# 9833YUANLI.net
KiCad netlist of a schematic drawn in EasyEDA
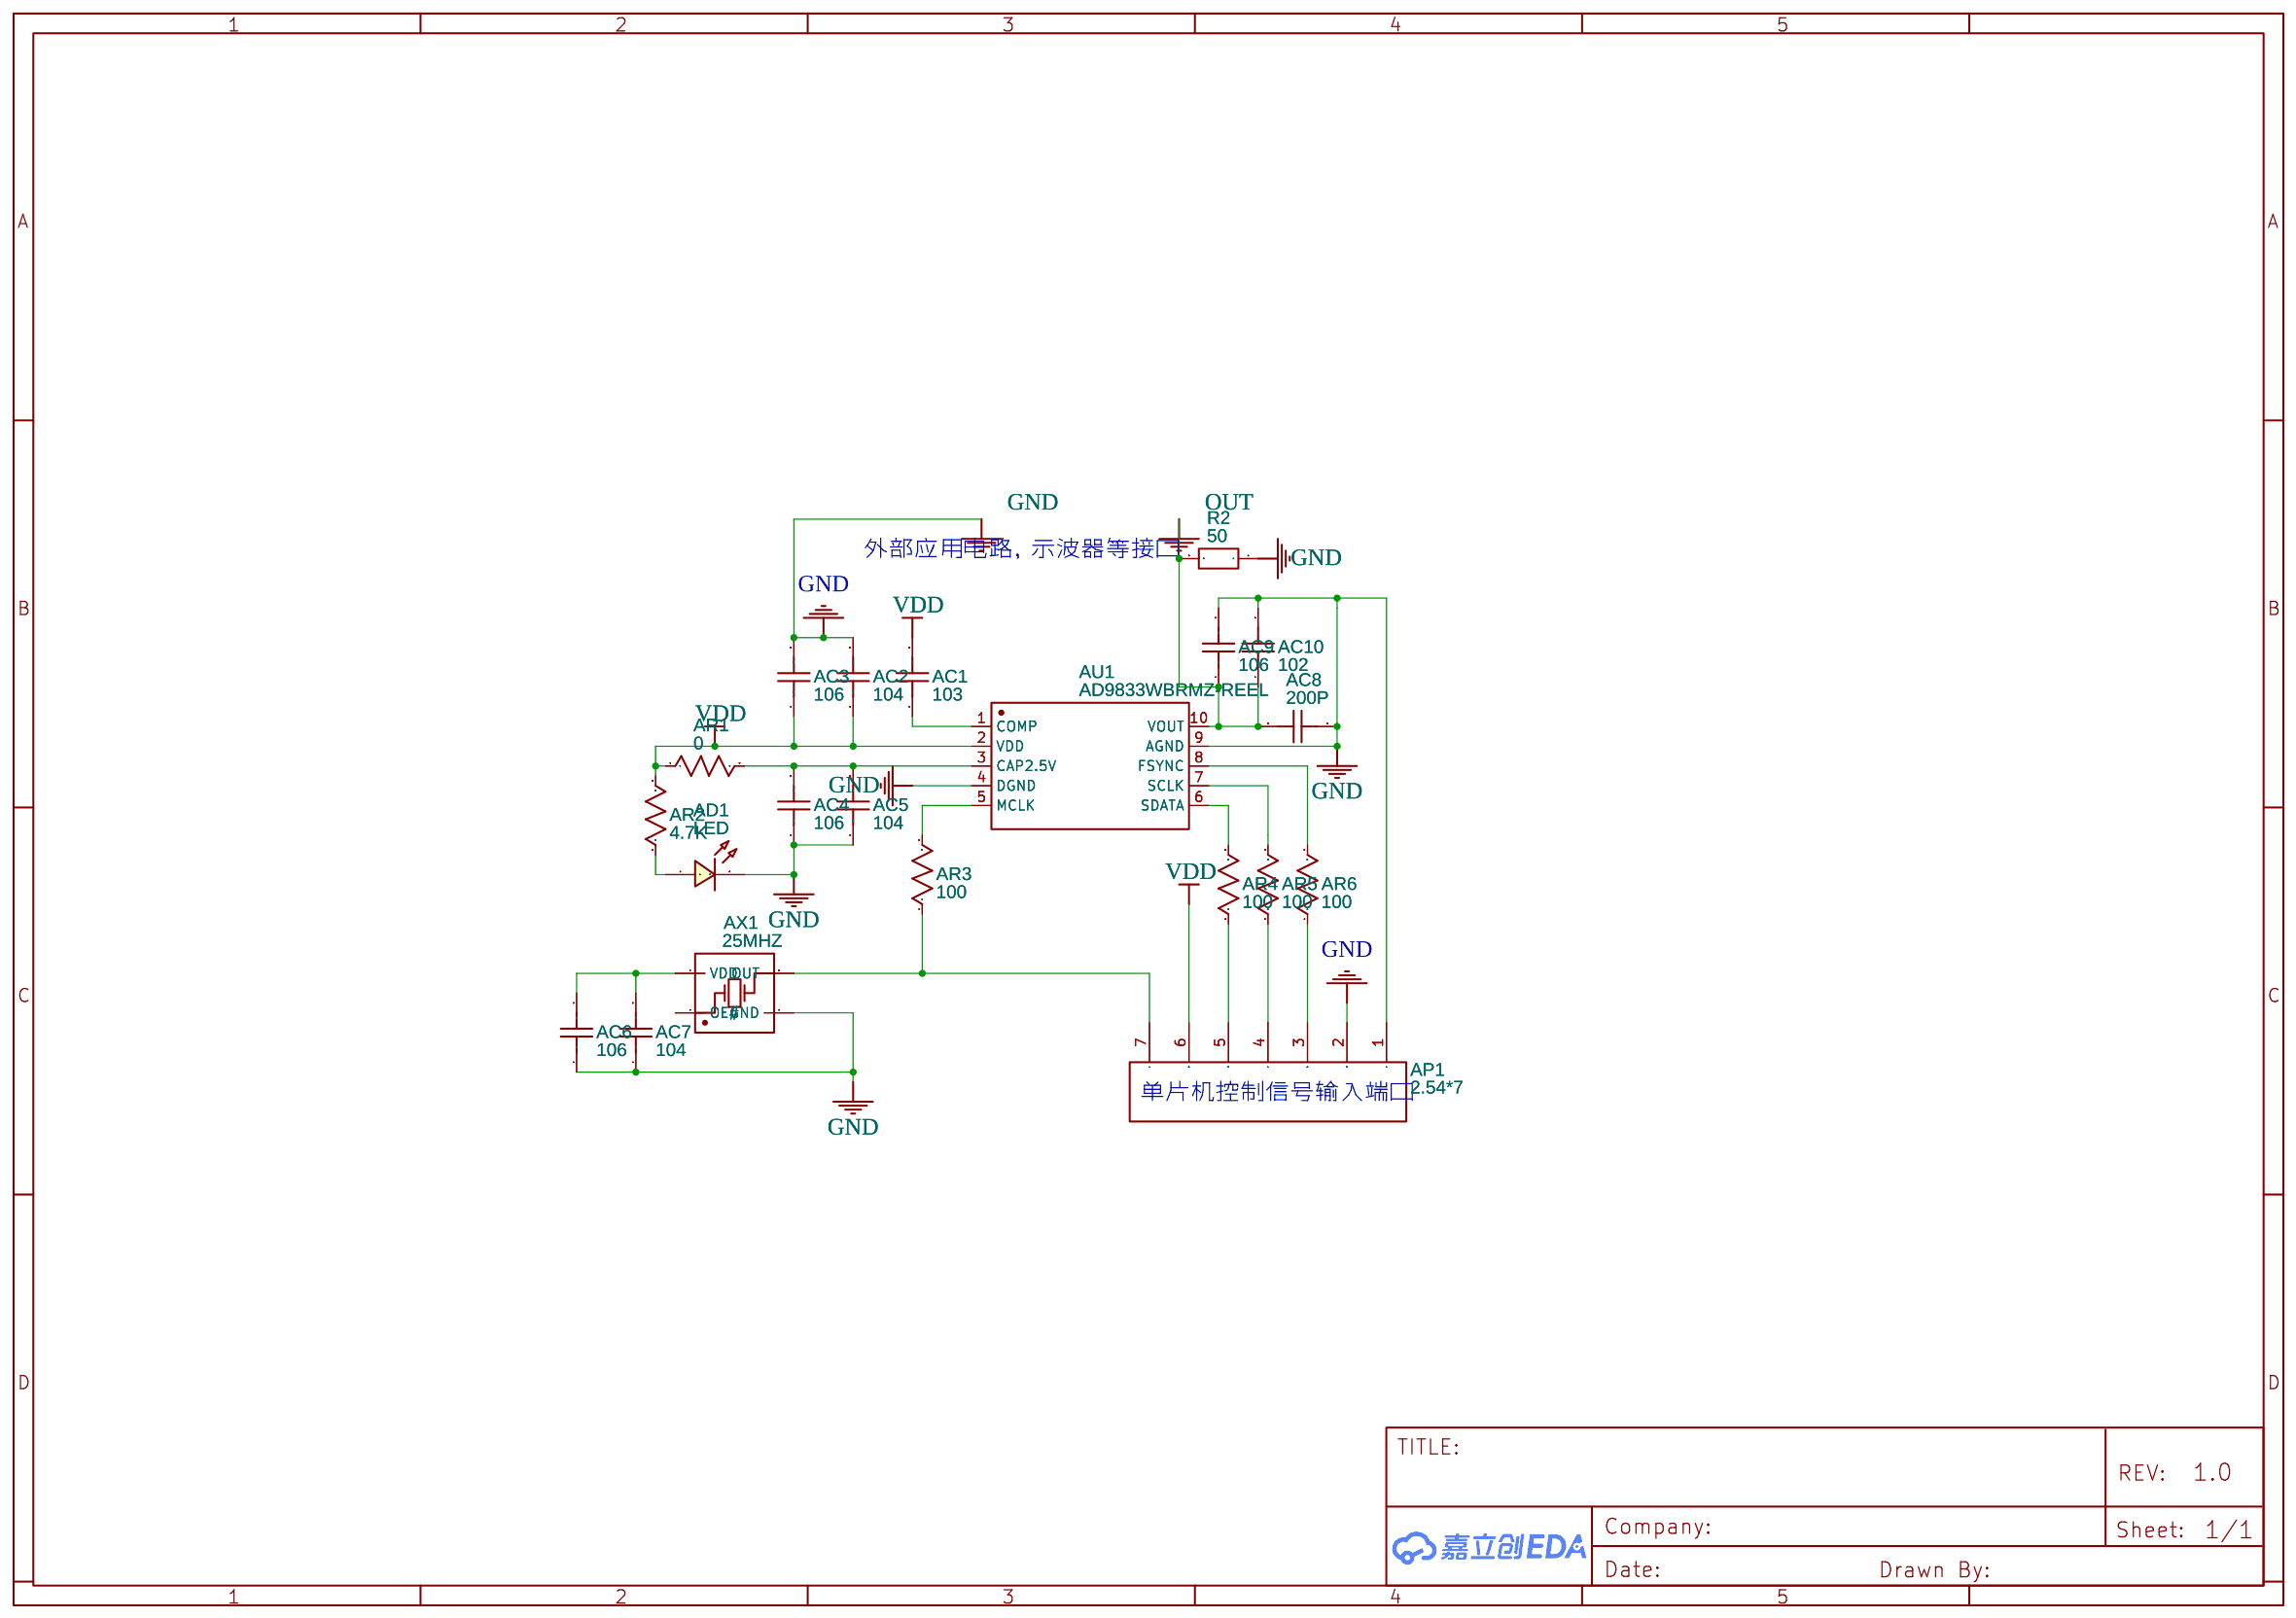
[diagram p0: schematic sheet]

(export (version "E")
  (design (tool "Eeschema 10.0.6"))
  (components
    (comp (ref "AC1") (value "103") (libsource (lib "") (part "C_0603_US")))
    (comp (ref "AC2") (value "104") (libsource (lib "") (part "C_0603_US")))
    (comp (ref "AC3") (value "106") (libsource (lib "") (part "C_0603_US")))
    (comp (ref "AC4") (value "106") (libsource (lib "") (part "C_0603_US")))
    (comp (ref "AC5") (value "104") (libsource (lib "") (part "C_0603_US")))
    (comp (ref "AC6") (value "106") (libsource (lib "") (part "C_0603_US")))
    (comp (ref "AC7") (value "104") (libsource (lib "") (part "C_0603_US")))
    (comp (ref "AC8") (value "200P") (libsource (lib "") (part "C_0603_US_1")))
    (comp (ref "AC9") (value "106") (libsource (lib "") (part "C_0603_US")))
    (comp (ref "AC10") (value "102") (libsource (lib "") (part "C_0603_US")))
    (comp (ref "AD1")
      (value "LED")
      (fields
        (field (name "Manufacturer Part") "17-21SURC/S530-A3/TR8")
        (field (name "Manufacturer") "EVERLIGHT(台湾亿光)")
      )
      (libsource (lib "") (part "LED-0805_R"))
    )
    (comp (ref "AP1") (value "2.54*7") (libsource (lib "") (part "2.54*7")))
    (comp (ref "AR1") (value "0") (libsource (lib "") (part "R_0603_US_1")))
    (comp (ref "AR2") (value "4.7K") (libsource (lib "") (part "R_0603_US")))
    (comp (ref "AR3") (value "100") (libsource (lib "") (part "R_0603_US")))
    (comp (ref "AR4") (value "100") (libsource (lib "") (part "R_0603_US")))
    (comp (ref "AR5") (value "100") (libsource (lib "") (part "R_0603_US")))
    (comp (ref "AR6") (value "100") (libsource (lib "") (part "R_0603_US")))
    (comp (ref "AU1") (value "AD9833WBRMZ-REEL") (libsource (lib "") (part "AD9833WBRMZ-REEL")))
    (comp (ref "AX1")
      (value "25MHZ")
      (fields (field (name "Manufacturer") "Harmony Elec"))
      (libsource (lib "") (part "HSO321S 25MHZ 3.3V"))
    )
    (comp (ref "R2") (value "50") (libsource (lib "") (part "R_0603_EU")))
  )
  (nets
    (net (code "1") (name "GND") (class "Default")
      (node (ref "AC10") (pin "2") (pinfunction "2_2") (pintype "unspecified"))
      (node (ref "AC2") (pin "2") (pinfunction "2_2") (pintype "unspecified"))
      (node (ref "AC3") (pin "2") (pinfunction "2_2") (pintype "unspecified"))
      (node (ref "AC4") (pin "1") (pinfunction "1_1") (pintype "unspecified"))
      (node (ref "AC5") (pin "1") (pinfunction "1_1") (pintype "unspecified"))
      (node (ref "AC6") (pin "1") (pinfunction "1_1") (pintype "unspecified"))
      (node (ref "AC7") (pin "1") (pinfunction "1_1") (pintype "unspecified"))
      (node (ref "AC8") (pin "1") (pinfunction "1_1") (pintype "unspecified"))
      (node (ref "AC9") (pin "2") (pinfunction "2_2") (pintype "unspecified"))
      (node (ref "AD1") (pin "2") (pinfunction "2_2") (pintype "unspecified"))
      (node (ref "AP1") (pin "1") (pinfunction "1_1") (pintype "unspecified"))
      (node (ref "AP1") (pin "2") (pinfunction "2_2") (pintype "unspecified"))
      (node (ref "AU1") (pin "4") (pinfunction "DGND_4") (pintype "unspecified"))
      (node (ref "AU1") (pin "9") (pinfunction "AGND_9") (pintype "unspecified"))
      (node (ref "AX1") (pin "2") (pinfunction "GND_2") (pintype "input"))
      (node (ref "R2") (pin "1") (pinfunction "1_1") (pintype "unspecified"))
    )
    (net (code "2") (name "Net-(AD1-Pad1)") (class "Default")
      (node (ref "AD1") (pin "1") (pinfunction "1_1") (pintype "unspecified"))
      (node (ref "AR2") (pin "1") (pinfunction "1_1") (pintype "unspecified"))
    )
    (net (code "3") (name "Net-(AP1-Pad3)") (class "Default")
      (node (ref "AP1") (pin "3") (pinfunction "3_3") (pintype "unspecified"))
      (node (ref "AR6") (pin "1") (pinfunction "1_1") (pintype "unspecified"))
    )
    (net (code "4") (name "Net-(AP1-Pad4)") (class "Default")
      (node (ref "AP1") (pin "4") (pinfunction "4_4") (pintype "unspecified"))
      (node (ref "AR5") (pin "1") (pinfunction "1_1") (pintype "unspecified"))
    )
    (net (code "5") (name "Net-(AP1-Pad5)") (class "Default")
      (node (ref "AP1") (pin "5") (pinfunction "5_5") (pintype "unspecified"))
      (node (ref "AR4") (pin "1") (pinfunction "1_1") (pintype "unspecified"))
    )
    (net (code "6") (name "Net-(AU1-CAP2.5V)") (class "Default")
      (node (ref "AC4") (pin "2") (pinfunction "2_2") (pintype "unspecified"))
      (node (ref "AC5") (pin "2") (pinfunction "2_2") (pintype "unspecified"))
      (node (ref "AR1") (pin "2") (pinfunction "2_2") (pintype "unspecified"))
      (node (ref "AU1") (pin "3") (pinfunction "CAP2.5V_3") (pintype "unspecified"))
    )
    (net (code "7") (name "Net-(AU1-COMP)") (class "Default")
      (node (ref "AC1") (pin "1") (pinfunction "1_1") (pintype "unspecified"))
      (node (ref "AU1") (pin "1") (pinfunction "COMP_1") (pintype "unspecified"))
    )
    (net (code "8") (name "Net-(AU1-FSYNC)") (class "Default")
      (node (ref "AR6") (pin "2") (pinfunction "2_2") (pintype "unspecified"))
      (node (ref "AU1") (pin "8") (pinfunction "FSYNC_8") (pintype "unspecified"))
    )
    (net (code "9") (name "Net-(AU1-MCLK)") (class "Default")
      (node (ref "AR3") (pin "2") (pinfunction "2_2") (pintype "unspecified"))
      (node (ref "AU1") (pin "5") (pinfunction "MCLK_5") (pintype "unspecified"))
    )
    (net (code "10") (name "Net-(AU1-SCLK)") (class "Default")
      (node (ref "AR5") (pin "2") (pinfunction "2_2") (pintype "unspecified"))
      (node (ref "AU1") (pin "7") (pinfunction "SCLK_7") (pintype "unspecified"))
    )
    (net (code "11") (name "Net-(AU1-SDATA)") (class "Default")
      (node (ref "AR4") (pin "2") (pinfunction "2_2") (pintype "unspecified"))
      (node (ref "AU1") (pin "6") (pinfunction "SDATA_6") (pintype "unspecified"))
    )
    (net (code "12") (name "Net-(AX1-OUT)") (class "Default")
      (node (ref "AP1") (pin "7") (pinfunction "7_7") (pintype "unspecified"))
      (node (ref "AR3") (pin "1") (pinfunction "1_1") (pintype "unspecified"))
      (node (ref "AX1") (pin "3") (pinfunction "OUT_3") (pintype "input"))
    )
    (net (code "13") (name "Net-(AX1-VDD)") (class "Default")
      (node (ref "AC6") (pin "2") (pinfunction "2_2") (pintype "unspecified"))
      (node (ref "AC7") (pin "2") (pinfunction "2_2") (pintype "unspecified"))
      (node (ref "AX1") (pin "4") (pinfunction "VDD_4") (pintype "input"))
    )
    (net (code "14") (name "OUT") (class "Default")
      (node (ref "AC10") (pin "1") (pinfunction "1_1") (pintype "unspecified"))
      (node (ref "AC8") (pin "2") (pinfunction "2_2") (pintype "unspecified"))
      (node (ref "AC9") (pin "1") (pinfunction "1_1") (pintype "unspecified"))
      (node (ref "AU1") (pin "10") (pinfunction "VOUT_10") (pintype "unspecified"))
      (node (ref "R2") (pin "2") (pinfunction "2_2") (pintype "unspecified"))
    )
    (net (code "15") (name "VDD") (class "Default")
      (node (ref "AC1") (pin "2") (pinfunction "2_2") (pintype "unspecified"))
      (node (ref "AC2") (pin "1") (pinfunction "1_1") (pintype "unspecified"))
      (node (ref "AC3") (pin "1") (pinfunction "1_1") (pintype "unspecified"))
      (node (ref "AP1") (pin "6") (pinfunction "6_6") (pintype "unspecified"))
      (node (ref "AR1") (pin "1") (pinfunction "1_1") (pintype "unspecified"))
      (node (ref "AR2") (pin "2") (pinfunction "2_2") (pintype "unspecified"))
      (node (ref "AU1") (pin "2") (pinfunction "VDD_2") (pintype "unspecified"))
    )
    (net (code "16") (name "unconnected-(AX1-OE#-Pad1)") (class "Default")
      (node (ref "AX1") (pin "1") (pinfunction "OE#_1") (pintype "input"))
    )
  )
)
